# LOGIC_SUPPLY.net
KiCad netlist of a schematic drawn in Altium Designer
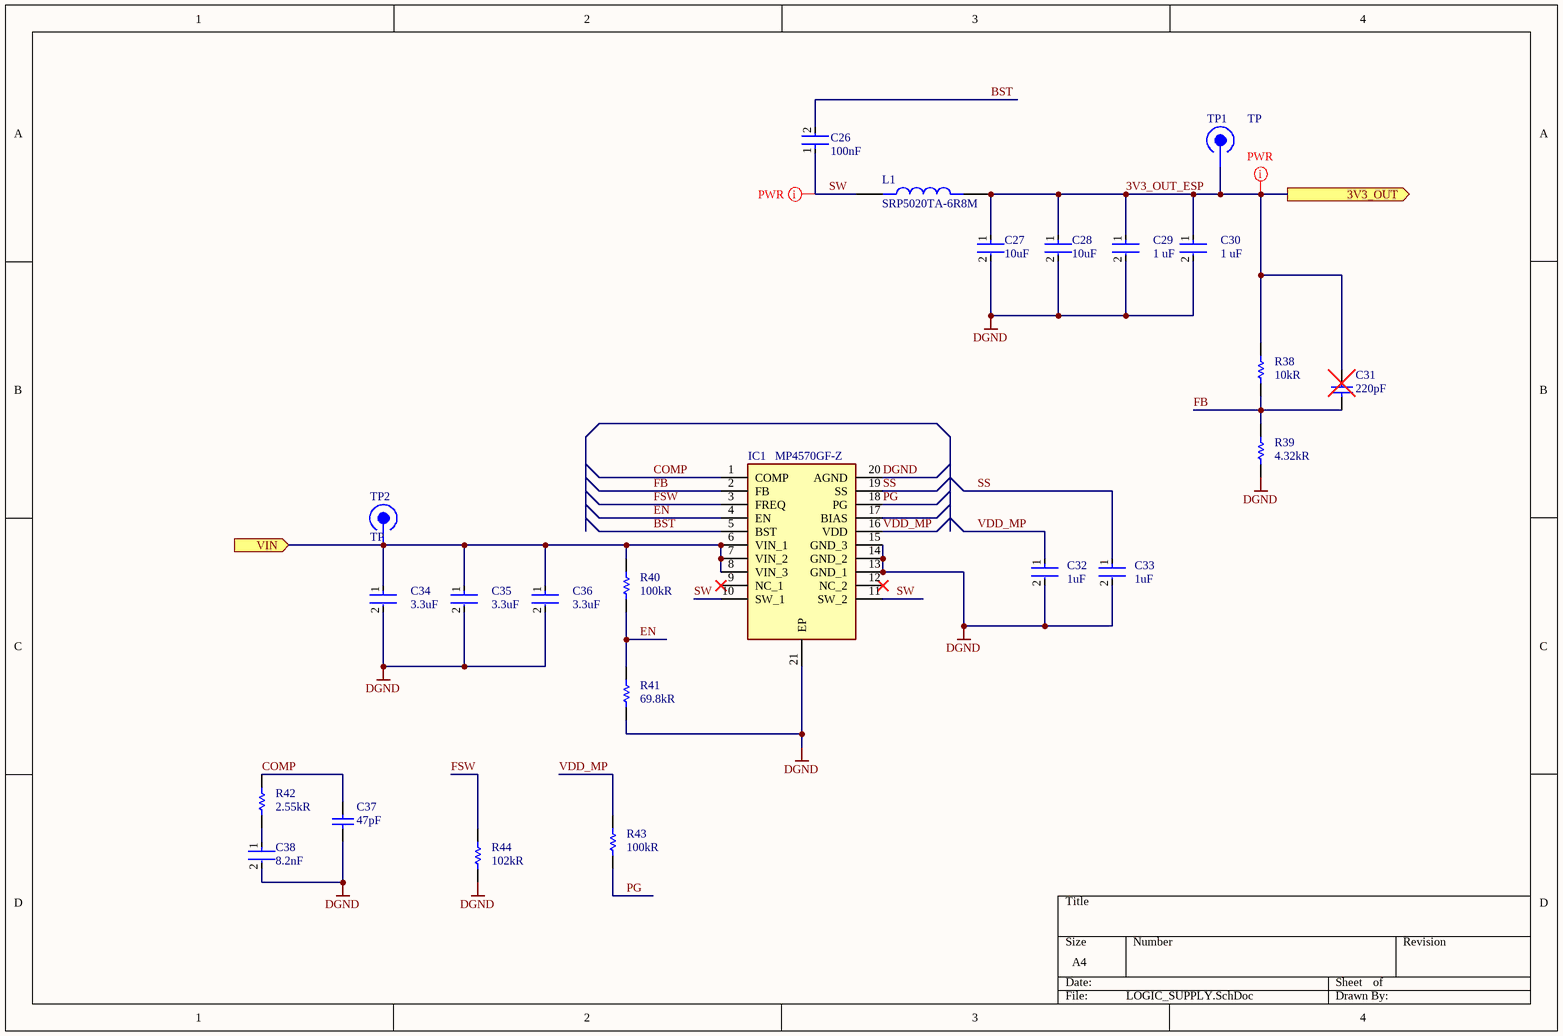
[diagram p0: LOGIC_SUPPLY.SchDoc]

(export (version "E")
  (design (tool "Eeschema 10.0.6"))
  (components
    (comp (ref "C26")
      (value "100nF")
      (footprint "FP-CC0402-IPC_B")
      (fields (field (name "Comment") "CC0402KRX7R9BB104"))
      (libsource (lib "Digital Shovel") (part "11868f565c42a9108669ba33697ecf6"))
    )
    (comp (ref "C27")
      (value "10uF")
      (footprint "FP-GRM21B-0_15-MFG")
      (fields (field (name "Comment") "GRM21BR71A106KA73L"))
      (libsource (lib "Digital Shovel") (part "b4654b650e69147ec39a6b967a45e02"))
    )
    (comp (ref "C28")
      (value "10uF")
      (footprint "FP-GRM21B-0_15-MFG")
      (fields (field (name "Comment") "GRM21BR71A106KA73L"))
      (libsource (lib "Digital Shovel") (part "b4654b650e69147ec39a6b967a45e02"))
    )
    (comp (ref "C29")
      (value "1 uF")
      (footprint "FP-CC0402-MFG")
      (description "CAP CER 1UF 10V X5R 0402")
      (fields
        (field (name "OCTOPART") "https://octopart.com/cc0402krx5r6bb105-yageo-42244620")
        (field (name "MANUFACTURER PART NUMBER") "CC0402KRX5R6BB105")
      )
      (libsource (lib "Altium Content Vault") (part "11868f565c42a9108669ba33697ecf6"))
    )
    (comp (ref "C30")
      (value "1 uF")
      (footprint "FP-CC0402-MFG")
      (description "CAP CER 1UF 10V X5R 0402")
      (fields
        (field (name "OCTOPART") "https://octopart.com/cc0402krx5r6bb105-yageo-42244620")
        (field (name "MANUFACTURER PART NUMBER") "CC0402KRX5R6BB105")
      )
      (libsource (lib "Altium Content Vault") (part "11868f565c42a9108669ba33697ecf6"))
    )
    (comp (ref "C31")
      (value "220pF")
      (footprint "CAPC1005X55X25LL05T10")
      (fields (field (name "MANUFACTURER") "Murata") (field (name "PART NUMBER") "GRM1555C1H221GA01J"))
      (libsource (lib "Altium Content Vault") (part "CAP"))
    )
    (comp (ref "C32")
      (value "GRM155R61E105KA12D")
      (footprint "FP-GRM155-0_05-IPC_B")
      (description "Chip Multilayer Ceramic Capacitors for General Purpose, 0402, 1.0uF, X5R, 15%, 10%, 25V")
      (fields
        (field (name "VOLTAGE") "25V")
        (field (name "TOLERANCE") "10%")
        (field (name "CAPACITANCE") "1uF")
      )
      (libsource (lib "Altium Content Vault") (part "02cd4be3c70576c341d710602a673aa"))
    )
    (comp (ref "C33")
      (value "GRM155R61E105KA12D")
      (footprint "FP-GRM155-0_05-IPC_B")
      (description "Chip Multilayer Ceramic Capacitors for General Purpose, 0402, 1.0uF, X5R, 15%, 10%, 25V")
      (fields
        (field (name "VOLTAGE") "25V")
        (field (name "TOLERANCE") "10%")
        (field (name "CAPACITANCE") "1uF")
      )
      (libsource (lib "Altium Content Vault") (part "02cd4be3c70576c341d710602a673aa"))
    )
    (comp (ref "C34")
      (value "3.3uF")
      (footprint "FP-C2012-125-0_2-MFG")
      (description "Multilayer Ceramic Capacitors 3.3μF ±10% 25V X7R SMD 0805")
      (fields (field (name "TOLERANCE") "10%") (field (name "Comment") "C2012X7R1E335K125AB"))
      (libsource (lib "Altium Content Vault") (part "b4654b650e69147ec39a6b967a45e02"))
    )
    (comp (ref "C35")
      (value "3.3uF")
      (footprint "FP-C2012-125-0_2-MFG")
      (description "Multilayer Ceramic Capacitors 3.3μF ±10% 25V X7R SMD 0805")
      (fields (field (name "TOLERANCE") "10%") (field (name "Comment") "C2012X7R1E335K125AB"))
      (libsource (lib "Altium Content Vault") (part "b4654b650e69147ec39a6b967a45e02"))
    )
    (comp (ref "C36")
      (value "3.3uF")
      (footprint "FP-C2012-125-0_2-MFG")
      (description "Multilayer Ceramic Capacitors 3.3μF ±10% 25V X7R SMD 0805")
      (fields (field (name "TOLERANCE") "10%") (field (name "Comment") "C2012X7R1E335K125AB"))
      (libsource (lib "Altium Content Vault") (part "b4654b650e69147ec39a6b967a45e02"))
    )
    (comp (ref "C37")
      (value "47pF")
      (footprint "CAPC1005X55X25LL05T10")
      (fields (field (name "MANUFACTURER") "Murata") (field (name "PART NUMBER") "GRM1555C1H470GA01D"))
      (libsource (lib "Altium Content Vault") (part "CAP"))
    )
    (comp (ref "C38")
      (value "8.2nF")
      (footprint "FP-GRM155-0_15-IPC_C")
      (description "Chip Multilayer Ceramic Capacitors for General Purpose, 0402, 8200pF, C0G, 30ppm/°C, 5%, 50V")
      (fields (field (name "Comment") "GRM1555C1H822JE01D"))
      (libsource (lib "Altium Content Vault") (part "b4654b650e69147ec39a6b967a45e02"))
    )
    (comp (ref "IC1")
      (value "MP4570GF-Z")
      (footprint "MP4570GF-Z-Footprint-1")
      (description "Switching Voltage Regulators 3A,4.5V-55V Input, Freqcy Programmable")
      (libsource (lib "Digital Shovel") (part "MP4570GF-Z-Symbol-1"))
    )
    (comp (ref "L1")
      (value "SRP5020TA-6R8M")
      (footprint "SRP5020TA-6R8M-Footprint-1")
      (description "General Purpose Inductor, 6.8uH, 20%, 1 Element, Metal Alloy Powder-Core, SMD, 2220")
      (libsource (lib "Digital Shovel") (part "SRP5020TA-6R8M-Symbol-1"))
    )
    (comp (ref "R38")
      (value "10kR")
      (footprint "RESC1005X40X25LL10T10")
      (fields (field (name "Comment") "RK73H1ETTP1002F"))
      (libsource (lib "Digital Shovel") (part "RES"))
    )
    (comp (ref "R39")
      (value "4.32kR")
      (footprint "RESC1005X40X25LL10T10")
      (fields
        (field (name "PART NUMBER") "RK73H1ETTP33R2F")
        (field (name "MANUFACTURER") "KOA Speer")
        (field (name "Comment") "RK73H1ETTP4321F")
      )
      (libsource (lib "Altium Content Vault") (part "RES"))
    )
    (comp (ref "R40")
      (value "100kR")
      (footprint "RESC1005X40X25NL10T10")
      (fields (field (name "Comment") "RK73H1ETTP1003F"))
      (libsource (lib "Digital Shovel") (part "RES"))
    )
    (comp (ref "R41")
      (value "69.8kR")
      (footprint "RESC1005X40X25NL10T10")
      (fields (field (name "MANUFACTURER") "KOA Speer") (field (name "PART NUMBER") "RK73H1ETTP6982F"))
      (libsource (lib "Altium Content Vault") (part "RES"))
    )
    (comp (ref "R42")
      (value "2.55kR")
      (footprint "RESC1005X40X25ML10T10")
      (fields (field (name "MANUFACTURER") "KOA Speer") (field (name "PART NUMBER") "RK73H1ETTP2551F"))
      (libsource (lib "Altium Content Vault") (part "RES"))
    )
    (comp (ref "R43")
      (value "100kR")
      (footprint "RESC1005X40X25LL10T10")
      (fields (field (name "Comment") "RK73H1ETTP1003F"))
      (libsource (lib "Digital Shovel") (part "RES"))
    )
    (comp (ref "R44")
      (value "102kR")
      (footprint "RESC1005X40X25ML10T10")
      (fields (field (name "MANUFACTURER") "KOA Speer") (field (name "PART NUMBER") "RK73H1ETTP1023F"))
      (libsource (lib "Altium Content Vault") (part "RES"))
    )
    (comp (ref "TP1")
      (value "TP")
      (footprint "TP-Footprint-1")
      (description "digital shovel test point")
      (libsource (lib "Digital Shovel") (part "TP-Symbol-1"))
    )
    (comp (ref "TP2")
      (value "TP")
      (footprint "TP-Footprint-1")
      (description "digital shovel test point")
      (libsource (lib "Digital Shovel") (part "TP-Symbol-1"))
    )
  )
  (nets
    (net (code "1") (name "/3V3_OUT_ESP") (class "Default")
      (node (ref "C27") (pin "1") (pinfunction "1_1") (pintype "passive"))
      (node (ref "C28") (pin "1") (pinfunction "1_1") (pintype "passive"))
      (node (ref "C29") (pin "1") (pinfunction "1_1") (pintype "passive"))
      (node (ref "C30") (pin "1") (pinfunction "1_1") (pintype "passive"))
      (node (ref "C31") (pin "2") (pinfunction "2_2") (pintype "passive"))
      (node (ref "L1") (pin "2") (pinfunction "2_2") (pintype "passive"))
      (node (ref "R38") (pin "2") (pinfunction "2_2") (pintype "passive"))
      (node (ref "TP1") (pin "1") (pintype "passive"))
    )
    (net (code "2") (name "/BST") (class "Default")
      (node (ref "C26") (pin "2") (pinfunction "2_2") (pintype "passive"))
      (node (ref "IC1") (pin "5") (pinfunction "BST_5") (pintype "passive"))
    )
    (net (code "3") (name "/COMP") (class "Default")
      (node (ref "C37") (pin "2") (pinfunction "2_2") (pintype "passive"))
      (node (ref "IC1") (pin "1") (pinfunction "COMP_1") (pintype "passive"))
      (node (ref "R42") (pin "2") (pinfunction "2_2") (pintype "passive"))
    )
    (net (code "4") (name "/EN") (class "Default")
      (node (ref "IC1") (pin "4") (pinfunction "EN_4") (pintype "passive"))
      (node (ref "R40") (pin "1") (pinfunction "1_1") (pintype "passive"))
      (node (ref "R41") (pin "2") (pinfunction "2_2") (pintype "passive"))
    )
    (net (code "5") (name "/FB") (class "Default")
      (node (ref "C31") (pin "1") (pinfunction "1_1") (pintype "passive"))
      (node (ref "IC1") (pin "2") (pinfunction "FB_2") (pintype "passive"))
      (node (ref "R38") (pin "1") (pinfunction "1_1") (pintype "passive"))
      (node (ref "R39") (pin "2") (pinfunction "2_2") (pintype "passive"))
    )
    (net (code "6") (name "/FSW") (class "Default")
      (node (ref "IC1") (pin "3") (pinfunction "FREQ_3") (pintype "passive"))
      (node (ref "R44") (pin "2") (pinfunction "2_2") (pintype "passive"))
    )
    (net (code "7") (name "/PG") (class "Default")
      (node (ref "IC1") (pin "18") (pinfunction "PG_18") (pintype "passive"))
      (node (ref "R43") (pin "1") (pinfunction "1_1") (pintype "passive"))
    )
    (net (code "8") (name "/SS") (class "Default")
      (node (ref "C33") (pin "1") (pinfunction "1_1") (pintype "passive"))
      (node (ref "IC1") (pin "19") (pinfunction "SS_19") (pintype "passive"))
    )
    (net (code "9") (name "/SW") (class "Default")
      (node (ref "C26") (pin "1") (pinfunction "1_1") (pintype "passive"))
      (node (ref "IC1") (pin "10") (pinfunction "SW_1_10") (pintype "passive"))
      (node (ref "IC1") (pin "11") (pinfunction "SW_2_11") (pintype "passive"))
      (node (ref "L1") (pin "1") (pinfunction "1_1") (pintype "passive"))
    )
    (net (code "10") (name "/VDD_MP") (class "Default")
      (node (ref "C32") (pin "1") (pinfunction "1_1") (pintype "passive"))
      (node (ref "IC1") (pin "16") (pinfunction "VDD_16") (pintype "passive"))
      (node (ref "R43") (pin "2") (pinfunction "2_2") (pintype "passive"))
    )
    (net (code "11") (name "/VIN") (class "Default")
      (node (ref "C34") (pin "1") (pinfunction "1_1") (pintype "passive"))
      (node (ref "C35") (pin "1") (pinfunction "1_1") (pintype "passive"))
      (node (ref "C36") (pin "1") (pinfunction "1_1") (pintype "passive"))
      (node (ref "IC1") (pin "6") (pinfunction "VIN_1_6") (pintype "passive"))
      (node (ref "IC1") (pin "7") (pinfunction "VIN_2_7") (pintype "passive"))
      (node (ref "IC1") (pin "8") (pinfunction "VIN_3_8") (pintype "passive"))
      (node (ref "R40") (pin "2") (pinfunction "2_2") (pintype "passive"))
      (node (ref "TP2") (pin "1") (pintype "passive"))
    )
    (net (code "12") (name "DGND") (class "Default")
      (node (ref "C27") (pin "2") (pinfunction "2_2") (pintype "passive"))
      (node (ref "C28") (pin "2") (pinfunction "2_2") (pintype "passive"))
      (node (ref "C29") (pin "2") (pinfunction "2_2") (pintype "passive"))
      (node (ref "C30") (pin "2") (pinfunction "2_2") (pintype "passive"))
      (node (ref "C32") (pin "2") (pinfunction "2_2") (pintype "passive"))
      (node (ref "C33") (pin "2") (pinfunction "2_2") (pintype "passive"))
      (node (ref "C34") (pin "2") (pinfunction "2_2") (pintype "passive"))
      (node (ref "C35") (pin "2") (pinfunction "2_2") (pintype "passive"))
      (node (ref "C36") (pin "2") (pinfunction "2_2") (pintype "passive"))
      (node (ref "C37") (pin "1") (pinfunction "1_1") (pintype "passive"))
      (node (ref "C38") (pin "2") (pinfunction "2_2") (pintype "passive"))
      (node (ref "IC1") (pin "13") (pinfunction "GND_1_13") (pintype "passive"))
      (node (ref "IC1") (pin "14") (pinfunction "GND_2_14") (pintype "passive"))
      (node (ref "IC1") (pin "15") (pinfunction "GND_3_15") (pintype "passive"))
      (node (ref "IC1") (pin "20") (pinfunction "AGND_20") (pintype "passive"))
      (node (ref "IC1") (pin "21") (pinfunction "EP_21") (pintype "passive"))
      (node (ref "R39") (pin "1") (pinfunction "1_1") (pintype "passive"))
      (node (ref "R41") (pin "1") (pinfunction "1_1") (pintype "passive"))
      (node (ref "R44") (pin "1") (pinfunction "1_1") (pintype "passive"))
    )
    (net (code "13") (name "Net-(C38-Pad1)") (class "Default")
      (node (ref "C38") (pin "1") (pinfunction "1_1") (pintype "passive"))
      (node (ref "R42") (pin "1") (pinfunction "1_1") (pintype "passive"))
    )
    (net (code "14") (name "unconnected-(IC1-BIAS-Pad17)") (class "Default")
      (node (ref "IC1") (pin "17") (pinfunction "BIAS_17") (pintype "passive"))
    )
    (net (code "15") (name "unconnected-(IC1-NC_1-Pad9)") (class "Default")
      (node (ref "IC1") (pin "9") (pinfunction "NC_1_9") (pintype "passive+no_connect"))
    )
    (net (code "16") (name "unconnected-(IC1-NC_2-Pad12)") (class "Default")
      (node (ref "IC1") (pin "12") (pinfunction "NC_2_12") (pintype "passive+no_connect"))
    )
  )
)
